# DRV8834.net
KiCad netlist of a schematic drawn in Altium Designer
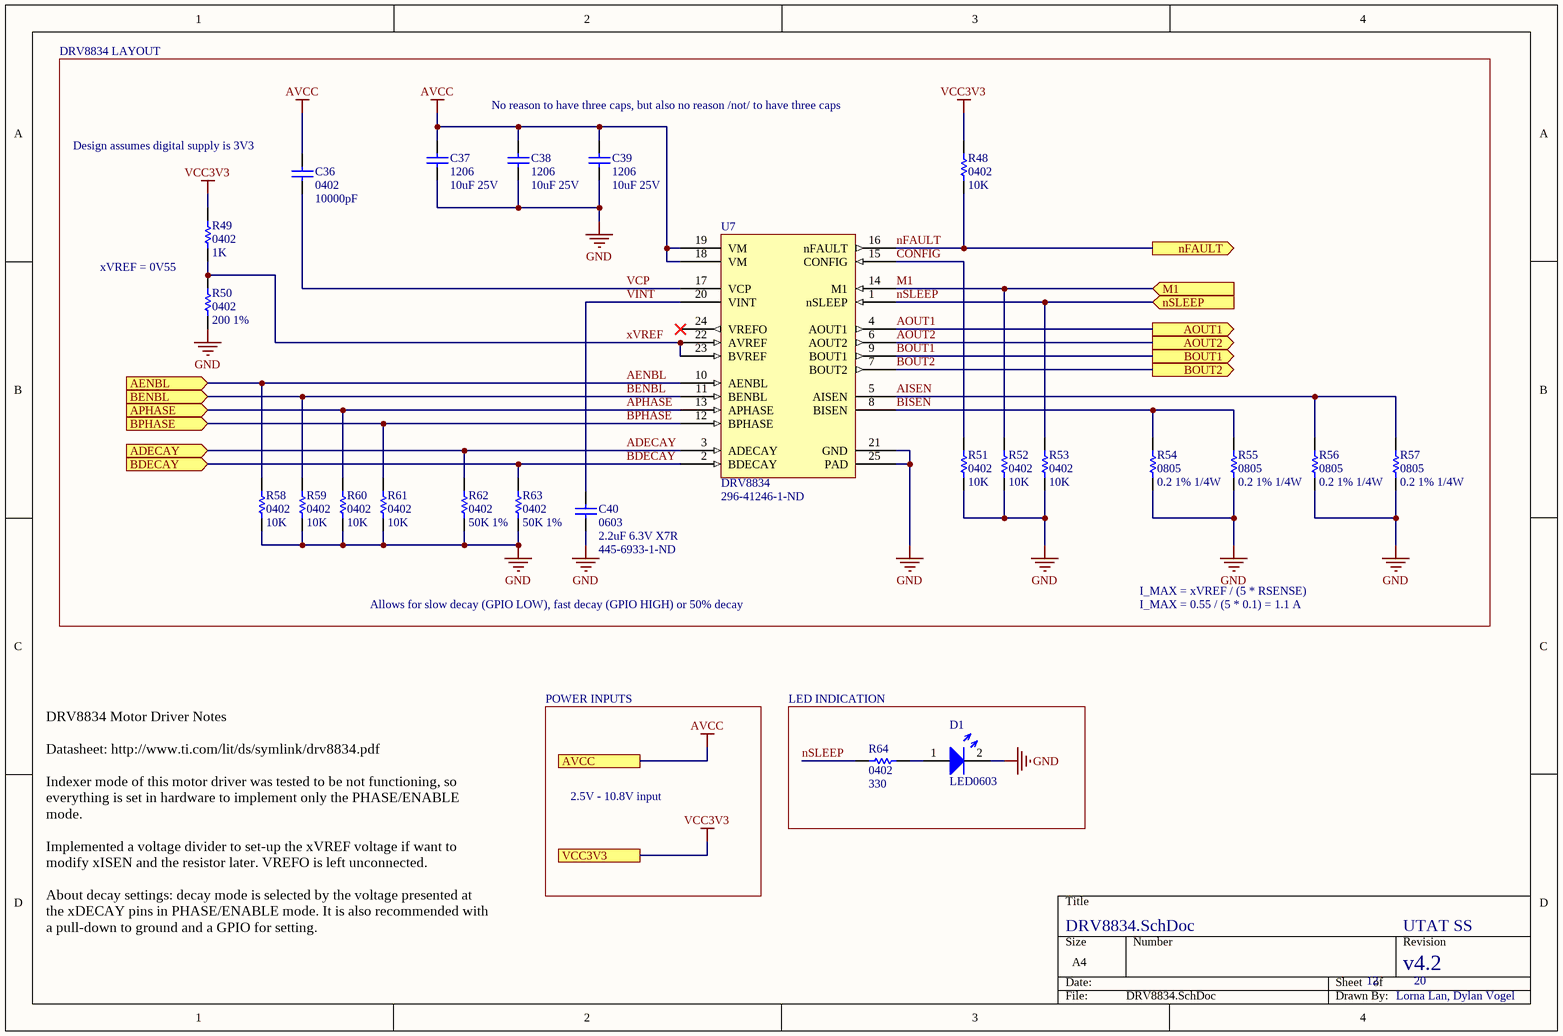
[diagram p0: DRV8834.SchDoc]

(export (version "E")
  (design (tool "Eeschema 10.0.6"))
  (components
    (comp (ref "C36")
      (value "0402")
      (footprint "CAP0402R")
      (description "Capacitor")
      (fields (field (name "ALTIUM_VALUE") "10000pF") (field (name "PUBLISHER") "Altium Limited"))
      (libsource (lib "Miscellaneous Devices") (part "Cap"))
    )
    (comp (ref "C37")
      (value "1206")
      (footprint "CAP1206R")
      (description "1206 capacitor")
      (fields (field (name "ALTIUM_VALUE") "10uF 25V"))
      (libsource (lib "heron-general") (part "CAP1206"))
    )
    (comp (ref "C38")
      (value "1206")
      (footprint "CAP1206R")
      (description "1206 capacitor")
      (fields (field (name "ALTIUM_VALUE") "10uF 25V"))
      (libsource (lib "heron-general") (part "CAP1206"))
    )
    (comp (ref "C39")
      (value "1206")
      (footprint "CAP1206R")
      (description "1206 capacitor")
      (fields (field (name "ALTIUM_VALUE") "10uF 25V"))
      (libsource (lib "heron-general") (part "CAP1206"))
    )
    (comp (ref "C40")
      (value "0603")
      (footprint "CAP0603R")
      (description "0603 capacitor")
      (fields
        (field (name "ALTIUM_VALUE") "2.2uF 6.3V X7R")
        (field (name "SUPPLIER PART NUMBER 1") "445-6933-1-ND")
      )
      (libsource (lib "heron-general") (part "CAP0603"))
    )
    (comp (ref "D1")
      (value "LED0603")
      (footprint "LED0603")
      (description "Generic 0603 LED. Use ChipLED from Osram for generic ones.")
      (libsource (lib "heron-general") (part "LED0603"))
    )
    (comp (ref "R48")
      (value "0402")
      (footprint "RES0402R")
      (description "0402 resistor")
      (fields (field (name "ALTIUM_VALUE") "10K"))
      (libsource (lib "heron-general") (part "RES0402"))
    )
    (comp (ref "R49")
      (value "0402")
      (footprint "RES0402R")
      (description "0402 resistor")
      (fields (field (name "ALTIUM_VALUE") "1K"))
      (libsource (lib "RES0402") (part "RES0402"))
    )
    (comp (ref "R50")
      (value "0402")
      (footprint "RES0402R")
      (description "0402 resistor")
      (fields (field (name "ALTIUM_VALUE") "200 1%"))
      (libsource (lib "heron-general") (part "RES0402"))
    )
    (comp (ref "R51")
      (value "0402")
      (footprint "RES0402R")
      (description "0402 resistor")
      (fields (field (name "ALTIUM_VALUE") "10K"))
      (libsource (lib "heron-general") (part "RES0402"))
    )
    (comp (ref "R52")
      (value "0402")
      (footprint "RES0402R")
      (description "0402 resistor")
      (fields (field (name "ALTIUM_VALUE") "10K"))
      (libsource (lib "heron-general") (part "RES0402"))
    )
    (comp (ref "R53")
      (value "0402")
      (footprint "RES0402R")
      (description "0402 resistor")
      (fields (field (name "ALTIUM_VALUE") "10K"))
      (libsource (lib "heron-general") (part "RES0402"))
    )
    (comp (ref "R54")
      (value "0805")
      (footprint "RES0805R")
      (description "0805 resistor")
      (fields (field (name "ALTIUM_VALUE") "0.2 1% 1/4W"))
      (libsource (lib "heron-general") (part "RES0805"))
    )
    (comp (ref "R55")
      (value "0805")
      (footprint "RES0805R")
      (description "0805 resistor")
      (fields (field (name "ALTIUM_VALUE") "0.2 1% 1/4W"))
      (libsource (lib "heron-general") (part "RES0805"))
    )
    (comp (ref "R56")
      (value "0805")
      (footprint "RES0805R")
      (description "0805 resistor")
      (fields (field (name "ALTIUM_VALUE") "0.2 1% 1/4W"))
      (libsource (lib "heron-general") (part "RES0805"))
    )
    (comp (ref "R57")
      (value "0805")
      (footprint "RES0805R")
      (description "0805 resistor")
      (fields (field (name "ALTIUM_VALUE") "0.2 1% 1/4W"))
      (libsource (lib "heron-general") (part "RES0805"))
    )
    (comp (ref "R58")
      (value "0402")
      (footprint "RES0402R")
      (description "0402 resistor")
      (fields (field (name "ALTIUM_VALUE") "10K"))
      (libsource (lib "heron-general") (part "RES0402"))
    )
    (comp (ref "R59")
      (value "0402")
      (footprint "RES0402R")
      (description "0402 resistor")
      (fields (field (name "ALTIUM_VALUE") "10K"))
      (libsource (lib "heron-general") (part "RES0402"))
    )
    (comp (ref "R60")
      (value "0402")
      (footprint "RES0402R")
      (description "0402 resistor")
      (fields (field (name "ALTIUM_VALUE") "10K"))
      (libsource (lib "heron-general") (part "RES0402"))
    )
    (comp (ref "R61")
      (value "0402")
      (footprint "RES0402R")
      (description "0402 resistor")
      (fields (field (name "ALTIUM_VALUE") "10K"))
      (libsource (lib "heron-general") (part "RES0402"))
    )
    (comp (ref "R62")
      (value "0402")
      (footprint "RES0402R")
      (description "0402 resistor")
      (fields (field (name "ALTIUM_VALUE") "50K 1%"))
      (libsource (lib "heron-general") (part "RES0402"))
    )
    (comp (ref "R63")
      (value "0402")
      (footprint "RES0402R")
      (description "0402 resistor")
      (fields (field (name "ALTIUM_VALUE") "50K 1%"))
      (libsource (lib "heron-general") (part "RES0402"))
    )
    (comp (ref "R64")
      (value "0402")
      (footprint "RES0402R")
      (description "0402 resistor")
      (fields
        (field (name "ALTIUM_VALUE") "330")
        (field (name "MANUFACTURER") "TE Connectivity")
        (field (name "MANUFACTURER PART NUMBER") "CRGCQ0402F330R")
      )
      (libsource (lib "heron-general") (part "RES0402"))
    )
    (comp (ref "U7")
      (value "DRV8834")
      (footprint "SOP65P640X120-25N")
      (description "Dual-bridge stepper or dc motor driver. 1.5A per coil with 2.5-10.8 V load supply.")
      (fields (field (name "SUPPLIER PART NUMBER 1") "296-41246-1-ND"))
      (libsource (lib "heron-general") (part "DRV8834"))
    )
  )
  (nets
    (net (code "1") (name "/ADECAY") (class "Default")
      (node (ref "R62") (pin "2") (pinfunction "2_2") (pintype "passive"))
      (node (ref "U7") (pin "3") (pinfunction "ADECAY_3") (pintype "input"))
    )
    (net (code "2") (name "/AENBL") (class "Default")
      (node (ref "R58") (pin "2") (pinfunction "2_2") (pintype "passive"))
      (node (ref "U7") (pin "10") (pinfunction "AENBL_10") (pintype "input"))
    )
    (net (code "3") (name "/AISEN") (class "Default")
      (node (ref "R56") (pin "2") (pinfunction "2_2") (pintype "passive"))
      (node (ref "R57") (pin "2") (pinfunction "2_2") (pintype "passive"))
      (node (ref "U7") (pin "5") (pinfunction "AISEN_5") (pintype "passive"))
    )
    (net (code "4") (name "/AOUT1") (class "Default")
      (node (ref "U7") (pin "4") (pinfunction "AOUT1_4") (pintype "output"))
    )
    (net (code "5") (name "/AOUT2") (class "Default")
      (node (ref "U7") (pin "6") (pinfunction "AOUT2_6") (pintype "output"))
    )
    (net (code "6") (name "/APHASE") (class "Default")
      (node (ref "R60") (pin "2") (pinfunction "2_2") (pintype "passive"))
      (node (ref "U7") (pin "13") (pinfunction "APHASE_13") (pintype "input"))
    )
    (net (code "7") (name "/BDECAY") (class "Default")
      (node (ref "R63") (pin "2") (pinfunction "2_2") (pintype "passive"))
      (node (ref "U7") (pin "2") (pinfunction "BDECAY_2") (pintype "input"))
    )
    (net (code "8") (name "/BENBL") (class "Default")
      (node (ref "R59") (pin "2") (pinfunction "2_2") (pintype "passive"))
      (node (ref "U7") (pin "11") (pinfunction "BENBL_11") (pintype "input"))
    )
    (net (code "9") (name "/BISEN") (class "Default")
      (node (ref "R54") (pin "2") (pinfunction "2_2") (pintype "passive"))
      (node (ref "R55") (pin "2") (pinfunction "2_2") (pintype "passive"))
      (node (ref "U7") (pin "8") (pinfunction "BISEN_8") (pintype "passive"))
    )
    (net (code "10") (name "/BOUT1") (class "Default")
      (node (ref "U7") (pin "9") (pinfunction "BOUT1_9") (pintype "output"))
    )
    (net (code "11") (name "/BOUT2") (class "Default")
      (node (ref "U7") (pin "7") (pinfunction "BOUT2_7") (pintype "output"))
    )
    (net (code "12") (name "/BPHASE") (class "Default")
      (node (ref "R61") (pin "2") (pinfunction "2_2") (pintype "passive"))
      (node (ref "U7") (pin "12") (pinfunction "BPHASE_12") (pintype "input"))
    )
    (net (code "13") (name "/CONFIG") (class "Default")
      (node (ref "R51") (pin "1") (pinfunction "1_1") (pintype "passive"))
      (node (ref "U7") (pin "15") (pinfunction "CONFIG_15") (pintype "input"))
    )
    (net (code "14") (name "/M1") (class "Default")
      (node (ref "R52") (pin "2") (pinfunction "2_2") (pintype "passive"))
      (node (ref "U7") (pin "14") (pinfunction "M1_14") (pintype "input"))
    )
    (net (code "15") (name "/VCP") (class "Default")
      (node (ref "C36") (pin "1") (pinfunction "1_1") (pintype "passive"))
      (node (ref "U7") (pin "17") (pinfunction "VCP_17") (pintype "power_in"))
    )
    (net (code "16") (name "/VINT") (class "Default")
      (node (ref "C40") (pin "1") (pinfunction "1_1") (pintype "passive"))
      (node (ref "U7") (pin "20") (pinfunction "VINT_20") (pintype "power_in"))
    )
    (net (code "17") (name "/nFAULT") (class "Default")
      (node (ref "R48") (pin "1") (pinfunction "1_1") (pintype "passive"))
      (node (ref "U7") (pin "16") (pinfunction "nFAULT_16") (pintype "output"))
    )
    (net (code "18") (name "/nSLEEP") (class "Default")
      (node (ref "R53") (pin "2") (pinfunction "2_2") (pintype "passive"))
      (node (ref "R64") (pin "2") (pinfunction "2_2") (pintype "passive"))
      (node (ref "U7") (pin "1") (pinfunction "nSLEEP_1") (pintype "input"))
    )
    (net (code "19") (name "/xVREF") (class "Default")
      (node (ref "R49") (pin "1") (pinfunction "1_1") (pintype "passive"))
      (node (ref "R50") (pin "2") (pinfunction "2_2") (pintype "passive"))
      (node (ref "U7") (pin "22") (pinfunction "AVREF_22") (pintype "input"))
      (node (ref "U7") (pin "23") (pinfunction "BVREF_23") (pintype "input"))
    )
    (net (code "20") (name "AVCC") (class "Default")
      (node (ref "C36") (pin "2") (pinfunction "2_2") (pintype "passive"))
      (node (ref "C37") (pin "2") (pinfunction "2_2") (pintype "passive"))
      (node (ref "C38") (pin "2") (pinfunction "2_2") (pintype "passive"))
      (node (ref "C39") (pin "2") (pinfunction "2_2") (pintype "passive"))
      (node (ref "U7") (pin "18") (pinfunction "VM_18") (pintype "power_in"))
      (node (ref "U7") (pin "19") (pinfunction "VM_19") (pintype "power_in"))
    )
    (net (code "21") (name "GND") (class "Default")
      (node (ref "C37") (pin "1") (pinfunction "1_1") (pintype "passive"))
      (node (ref "C38") (pin "1") (pinfunction "1_1") (pintype "passive"))
      (node (ref "C39") (pin "1") (pinfunction "1_1") (pintype "passive"))
      (node (ref "C40") (pin "2") (pinfunction "2_2") (pintype "passive"))
      (node (ref "D1") (pin "2") (pinfunction "2_2") (pintype "passive"))
      (node (ref "R50") (pin "1") (pinfunction "1_1") (pintype "passive"))
      (node (ref "R51") (pin "2") (pinfunction "2_2") (pintype "passive"))
      (node (ref "R52") (pin "1") (pinfunction "1_1") (pintype "passive"))
      (node (ref "R53") (pin "1") (pinfunction "1_1") (pintype "passive"))
      (node (ref "R54") (pin "1") (pinfunction "1_1") (pintype "passive"))
      (node (ref "R55") (pin "1") (pinfunction "1_1") (pintype "passive"))
      (node (ref "R56") (pin "1") (pinfunction "1_1") (pintype "passive"))
      (node (ref "R57") (pin "1") (pinfunction "1_1") (pintype "passive"))
      (node (ref "R58") (pin "1") (pinfunction "1_1") (pintype "passive"))
      (node (ref "R59") (pin "1") (pinfunction "1_1") (pintype "passive"))
      (node (ref "R60") (pin "1") (pinfunction "1_1") (pintype "passive"))
      (node (ref "R61") (pin "1") (pinfunction "1_1") (pintype "passive"))
      (node (ref "R62") (pin "1") (pinfunction "1_1") (pintype "passive"))
      (node (ref "R63") (pin "1") (pinfunction "1_1") (pintype "passive"))
      (node (ref "U7") (pin "21") (pinfunction "GND_21") (pintype "power_in"))
      (node (ref "U7") (pin "25") (pinfunction "PAD_25") (pintype "power_in"))
    )
    (net (code "22") (name "Net-(D1-Pad1)") (class "Default")
      (node (ref "D1") (pin "1") (pinfunction "1_1") (pintype "passive"))
      (node (ref "R64") (pin "1") (pinfunction "1_1") (pintype "passive"))
    )
    (net (code "23") (name "VCC3V3") (class "Default")
      (node (ref "R48") (pin "2") (pinfunction "2_2") (pintype "passive"))
      (node (ref "R49") (pin "2") (pinfunction "2_2") (pintype "passive"))
    )
    (net (code "24") (name "unconnected-(U7-VREFO-Pad24)") (class "Default")
      (node (ref "U7") (pin "24") (pinfunction "VREFO_24") (pintype "output+no_connect"))
    )
  )
)
